# TPS55340-testBoard.net
KiCad netlist of a schematic drawn in EAGLE
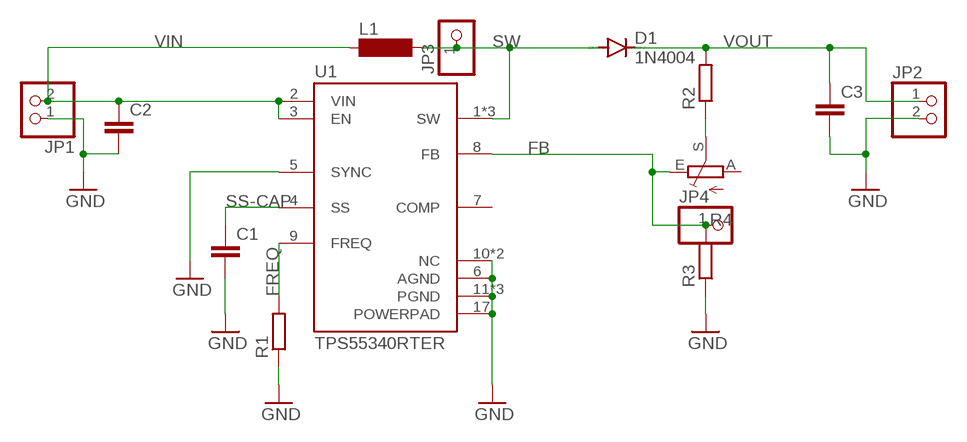
[diagram p0: schematic, sheet 1]

(export (version "E")
  (design (tool "Eeschema 10.0.6"))
  (components
    (comp (ref "C1")
      (value "C5/5")
      (footprint "eagle-import:C5B5")
      (libsource (lib "eagle-import") (part "C5/5"))
    )
    (comp (ref "C2")
      (value "C5/5")
      (footprint "eagle-import:C5B5")
      (libsource (lib "eagle-import") (part "C5/5"))
    )
    (comp (ref "C3")
      (value "C5/5")
      (footprint "eagle-import:C5B5")
      (libsource (lib "eagle-import") (part "C5/5"))
    )
    (comp (ref "D1")
      (value "1N4004")
      (footprint "eagle-import:DO41-10")
      (libsource (lib "eagle-import") (part "1N4004"))
    )
    (comp (ref "JP1")
      (value "PINHD-1X2/90")
      (footprint "eagle-import:1X02_90")
      (libsource (lib "eagle-import") (part "PINHD-1X2/90"))
    )
    (comp (ref "JP2")
      (value "PINHD-1X2/90")
      (footprint "eagle-import:1X02_90")
      (libsource (lib "eagle-import") (part "PINHD-1X2/90"))
    )
    (comp (ref "JP3")
      (value "PINHD-1X1")
      (footprint "eagle-import:1X01")
      (libsource (lib "eagle-import") (part "PINHD-1X1"))
    )
    (comp (ref "JP4")
      (value "PINHD-1X1")
      (footprint "eagle-import:1X01")
      (libsource (lib "eagle-import") (part "PINHD-1X1"))
    )
    (comp (ref "L1")
      (value "BS75")
      (footprint "eagle-import:BS75")
      (libsource (lib "eagle-import") (part "BS75"))
    )
    (comp (ref "R1")
      (value "R-EU_VMTB60")
      (footprint "eagle-import:VMTB60")
      (libsource (lib "eagle-import") (part "R-EU_VMTB60"))
    )
    (comp (ref "R2")
      (value "R-EU_VMTB60")
      (footprint "eagle-import:VMTB60")
      (libsource (lib "eagle-import") (part "R-EU_VMTB60"))
    )
    (comp (ref "R3")
      (value "R-EU_VMTB60")
      (footprint "eagle-import:VMTB60")
      (libsource (lib "eagle-import") (part "R-EU_VMTB60"))
    )
    (comp (ref "R4")
      (value "TRIM_EU-CA9V")
      (footprint "eagle-import:CA9V")
      (libsource (lib "eagle-import") (part "TRIM_EU-CA9V"))
    )
    (comp (ref "U1")
      (value "TPS55340RTER")
      (footprint "eagle-import:QFN50P300X300X80-17N")
      (fields (field (name "MF") "Texas Instruments"))
      (libsource (lib "eagle-import") (part "TPS55340RTER"))
    )
  )
  (nets
    (net (code "1") (name "/FB") (class "Default")
      (node (ref "JP4") (pin "1") (pinfunction "1_1") (pintype "passive"))
      (node (ref "R3") (pin "2") (pinfunction "2_2") (pintype "passive"))
      (node (ref "R4") (pin "E") (pinfunction "E_E") (pintype "passive"))
      (node (ref "U1") (pin "8") (pinfunction "FB_8") (pintype "input"))
    )
    (net (code "2") (name "/FREQ") (class "Default")
      (node (ref "R1") (pin "2") (pinfunction "2_2") (pintype "passive"))
      (node (ref "U1") (pin "9") (pinfunction "FREQ_9") (pintype "input"))
    )
    (net (code "3") (name "/SS-CAP") (class "Default")
      (node (ref "C1") (pin "1") (pinfunction "1_1") (pintype "passive"))
      (node (ref "U1") (pin "4") (pinfunction "SS_4") (pintype "input"))
    )
    (net (code "4") (name "/SW") (class "Default")
      (node (ref "D1") (pin "A") (pinfunction "A_A") (pintype "passive"))
      (node (ref "JP3") (pin "1") (pinfunction "1_1") (pintype "passive"))
      (node (ref "L1") (pin "2") (pinfunction "2_2") (pintype "passive"))
      (node (ref "U1") (pin "1") (pinfunction "SW_1") (pintype "output"))
      (node (ref "U1") (pin "15") (pinfunction "SW_15") (pintype "output"))
      (node (ref "U1") (pin "16") (pinfunction "SW_16") (pintype "output"))
    )
    (net (code "5") (name "/VIN") (class "Default")
      (node (ref "C2") (pin "1") (pinfunction "1_1") (pintype "passive"))
      (node (ref "JP1") (pin "2") (pinfunction "2_2") (pintype "passive"))
      (node (ref "L1") (pin "1") (pinfunction "1_1") (pintype "passive"))
      (node (ref "U1") (pin "2") (pinfunction "VIN_2") (pintype "power_in"))
      (node (ref "U1") (pin "3") (pinfunction "EN_3") (pintype "input"))
    )
    (net (code "6") (name "/VOUT") (class "Default")
      (node (ref "C3") (pin "1") (pinfunction "1_1") (pintype "passive"))
      (node (ref "D1") (pin "C") (pinfunction "C_C") (pintype "passive"))
      (node (ref "JP2") (pin "1") (pinfunction "1_1") (pintype "passive"))
      (node (ref "R2") (pin "2") (pinfunction "2_2") (pintype "passive"))
    )
    (net (code "7") (name "GND") (class "Default")
      (node (ref "C1") (pin "2") (pinfunction "2_2") (pintype "passive"))
      (node (ref "C2") (pin "2") (pinfunction "2_2") (pintype "passive"))
      (node (ref "C3") (pin "2") (pinfunction "2_2") (pintype "passive"))
      (node (ref "JP1") (pin "1") (pinfunction "1_1") (pintype "passive"))
      (node (ref "JP2") (pin "2") (pinfunction "2_2") (pintype "passive"))
      (node (ref "R1") (pin "1") (pinfunction "1_1") (pintype "passive"))
      (node (ref "R3") (pin "1") (pinfunction "1_1") (pintype "passive"))
      (node (ref "U1") (pin "10") (pinfunction "NC_10") (pintype "power_in"))
      (node (ref "U1") (pin "11") (pinfunction "PGND_11") (pintype "power_in"))
      (node (ref "U1") (pin "12") (pinfunction "PGND_12") (pintype "power_in"))
      (node (ref "U1") (pin "13") (pinfunction "PGND_13") (pintype "power_in"))
      (node (ref "U1") (pin "14") (pinfunction "NC_14") (pintype "power_in"))
      (node (ref "U1") (pin "17") (pinfunction "POWERPAD_17") (pintype "power_in"))
      (node (ref "U1") (pin "5") (pinfunction "SYNC_5") (pintype "input"))
      (node (ref "U1") (pin "6") (pinfunction "AGND_6") (pintype "power_in"))
    )
    (net (code "8") (name "Net-(R2-Pad1)") (class "Default")
      (node (ref "R2") (pin "1") (pinfunction "1_1") (pintype "passive"))
      (node (ref "R4") (pin "S") (pinfunction "S_S") (pintype "passive"))
    )
    (net (code "9") (name "unconnected-(R4-PadA)") (class "Default")
      (node (ref "R4") (pin "A") (pinfunction "A_A") (pintype "passive"))
    )
    (net (code "10") (name "unconnected-(U1-COMP-Pad7)") (class "Default")
      (node (ref "U1") (pin "7") (pinfunction "COMP_7") (pintype "output"))
    )
  )
)
